# SCH_Resert_Circuit_-_1_0_2021-10-20.net
KiCad netlist of a schematic drawn in EasyEDA
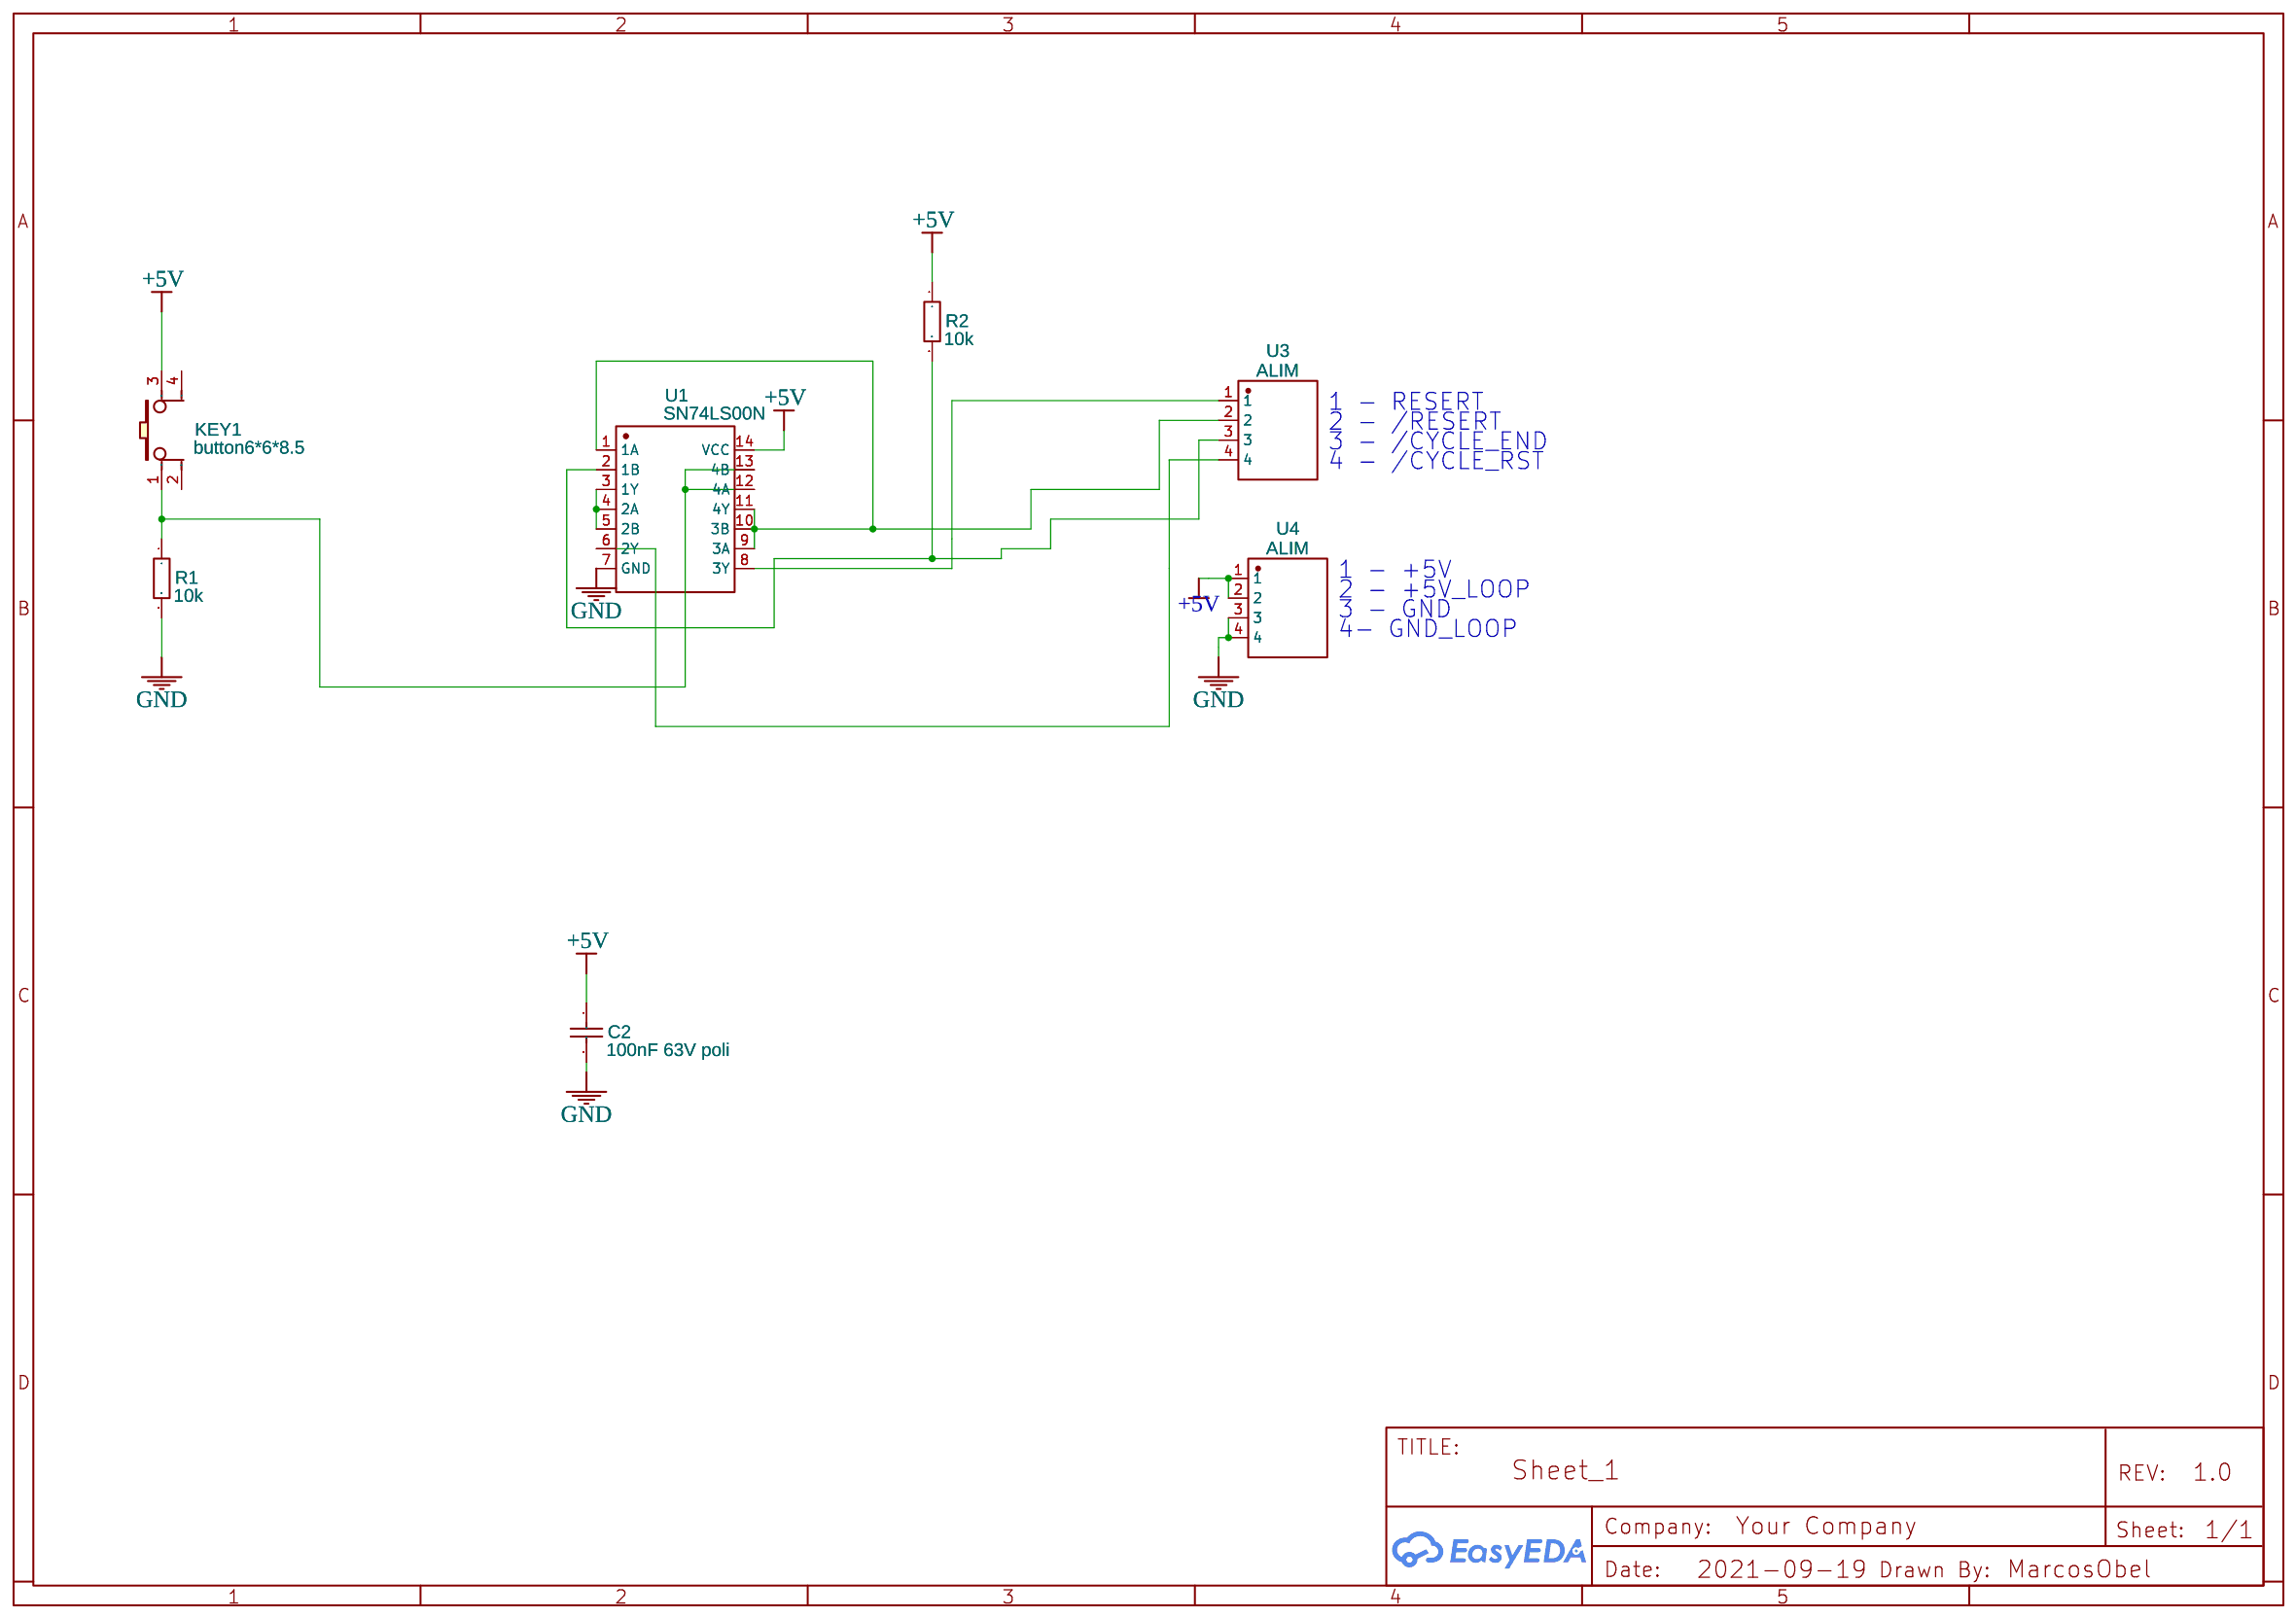
[diagram p0: schematic sheet]

(export (version "E")
  (design (tool "Eeschema 10.0.6"))
  (components
    (comp (ref "C2")
      (value "100nF 63V poli")
      (fields
        (field (name "BOM_Manufacturer Part") "0.01uF(103) 100V")
        (field (name "BOM_Supplier Part") "C10722")
      )
      (libsource (lib "") (part "0.01uF(103) 100V"))
    )
    (comp (ref "KEY1")
      (value "button6*6*8.5")
      (fields (field (name "BOM_Supplier Part") "C59980"))
      (libsource (lib "") (part "button6*6*8.5"))
    )
    (comp (ref "R1")
      (value "10k")
      (fields (field (name "BOM_Supplier Part") "C119997"))
      (libsource (lib "") (part "CF1/4W-3.9Ω±5% T52"))
    )
    (comp (ref "R2")
      (value "10k")
      (fields (field (name "BOM_Supplier Part") "C119997"))
      (libsource (lib "") (part "CF1/4W-3.9Ω±5% T52"))
    )
    (comp (ref "U1")
      (value "SN74LS00N")
      (fields (field (name "BOM_Supplier Part") "C181629"))
      (libsource (lib "") (part "SN74LS00N"))
    )
    (comp (ref "U3")
      (value "ALIM")
      (fields (field (name "BOM_Manufacturer Part") "171825-4") (field (name "BOM_Supplier Part") "C210162"))
      (libsource (lib "") (part "171825-4"))
    )
    (comp (ref "U4")
      (value "ALIM")
      (fields (field (name "BOM_Manufacturer Part") "171825-4") (field (name "BOM_Supplier Part") "C210162"))
      (libsource (lib "") (part "171825-4"))
    )
  )
  (nets
    (net (code "1") (name "+5V") (class "Default")
      (node (ref "C2") (pin "1") (pinfunction "1_1") (pintype "input"))
      (node (ref "KEY1") (pin "3") (pinfunction "3_3") (pintype "input"))
      (node (ref "R2") (pin "1") (pinfunction "1_1") (pintype "unspecified"))
      (node (ref "U1") (pin "14") (pinfunction "VCC_14") (pintype "unspecified"))
      (node (ref "U4") (pin "1") (pinfunction "1_1") (pintype "unspecified"))
      (node (ref "U4") (pin "2") (pinfunction "2_2") (pintype "unspecified"))
    )
    (net (code "2") (name "GND") (class "Default")
      (node (ref "C2") (pin "2") (pinfunction "2_2") (pintype "input"))
      (node (ref "R1") (pin "2") (pinfunction "2_2") (pintype "unspecified"))
      (node (ref "U1") (pin "7") (pinfunction "GND_7") (pintype "unspecified"))
      (node (ref "U4") (pin "3") (pinfunction "3_3") (pintype "unspecified"))
      (node (ref "U4") (pin "4") (pinfunction "4_4") (pintype "unspecified"))
    )
    (net (code "3") (name "Net-(U1-1A)") (class "Default")
      (node (ref "U1") (pin "1") (pinfunction "1A_1") (pintype "unspecified"))
      (node (ref "U1") (pin "10") (pinfunction "3B_10") (pintype "unspecified"))
      (node (ref "U1") (pin "11") (pinfunction "4Y_11") (pintype "unspecified"))
      (node (ref "U1") (pin "9") (pinfunction "3A_9") (pintype "unspecified"))
      (node (ref "U3") (pin "2") (pinfunction "2_2") (pintype "unspecified"))
    )
    (net (code "4") (name "Net-(U1-1B)") (class "Default")
      (node (ref "R2") (pin "2") (pinfunction "2_2") (pintype "unspecified"))
      (node (ref "U1") (pin "2") (pinfunction "1B_2") (pintype "unspecified"))
      (node (ref "U3") (pin "3") (pinfunction "3_3") (pintype "unspecified"))
    )
    (net (code "5") (name "Net-(U1-1Y)") (class "Default")
      (node (ref "U1") (pin "3") (pinfunction "1Y_3") (pintype "unspecified"))
      (node (ref "U1") (pin "4") (pinfunction "2A_4") (pintype "unspecified"))
      (node (ref "U1") (pin "5") (pinfunction "2B_5") (pintype "unspecified"))
    )
    (net (code "6") (name "Net-(U1-2Y)") (class "Default")
      (node (ref "U1") (pin "6") (pinfunction "2Y_6") (pintype "unspecified"))
      (node (ref "U3") (pin "4") (pinfunction "4_4") (pintype "unspecified"))
    )
    (net (code "7") (name "Net-(U1-3Y)") (class "Default")
      (node (ref "U1") (pin "8") (pinfunction "3Y_8") (pintype "unspecified"))
      (node (ref "U3") (pin "1") (pinfunction "1_1") (pintype "unspecified"))
    )
    (net (code "8") (name "Net-(U1-4A)") (class "Default")
      (node (ref "KEY1") (pin "1") (pinfunction "1_1") (pintype "input"))
      (node (ref "R1") (pin "1") (pinfunction "1_1") (pintype "unspecified"))
      (node (ref "U1") (pin "12") (pinfunction "4A_12") (pintype "unspecified"))
      (node (ref "U1") (pin "13") (pinfunction "4B_13") (pintype "unspecified"))
    )
    (net (code "9") (name "unconnected-(KEY1-Pad2)") (class "Default")
      (node (ref "KEY1") (pin "2") (pinfunction "2_2") (pintype "input"))
    )
    (net (code "10") (name "unconnected-(KEY1-Pad4)") (class "Default")
      (node (ref "KEY1") (pin "4") (pinfunction "4_4") (pintype "input"))
    )
  )
)
